# open-rally-computer.net
KiCad netlist of a schematic drawn in EasyEDA
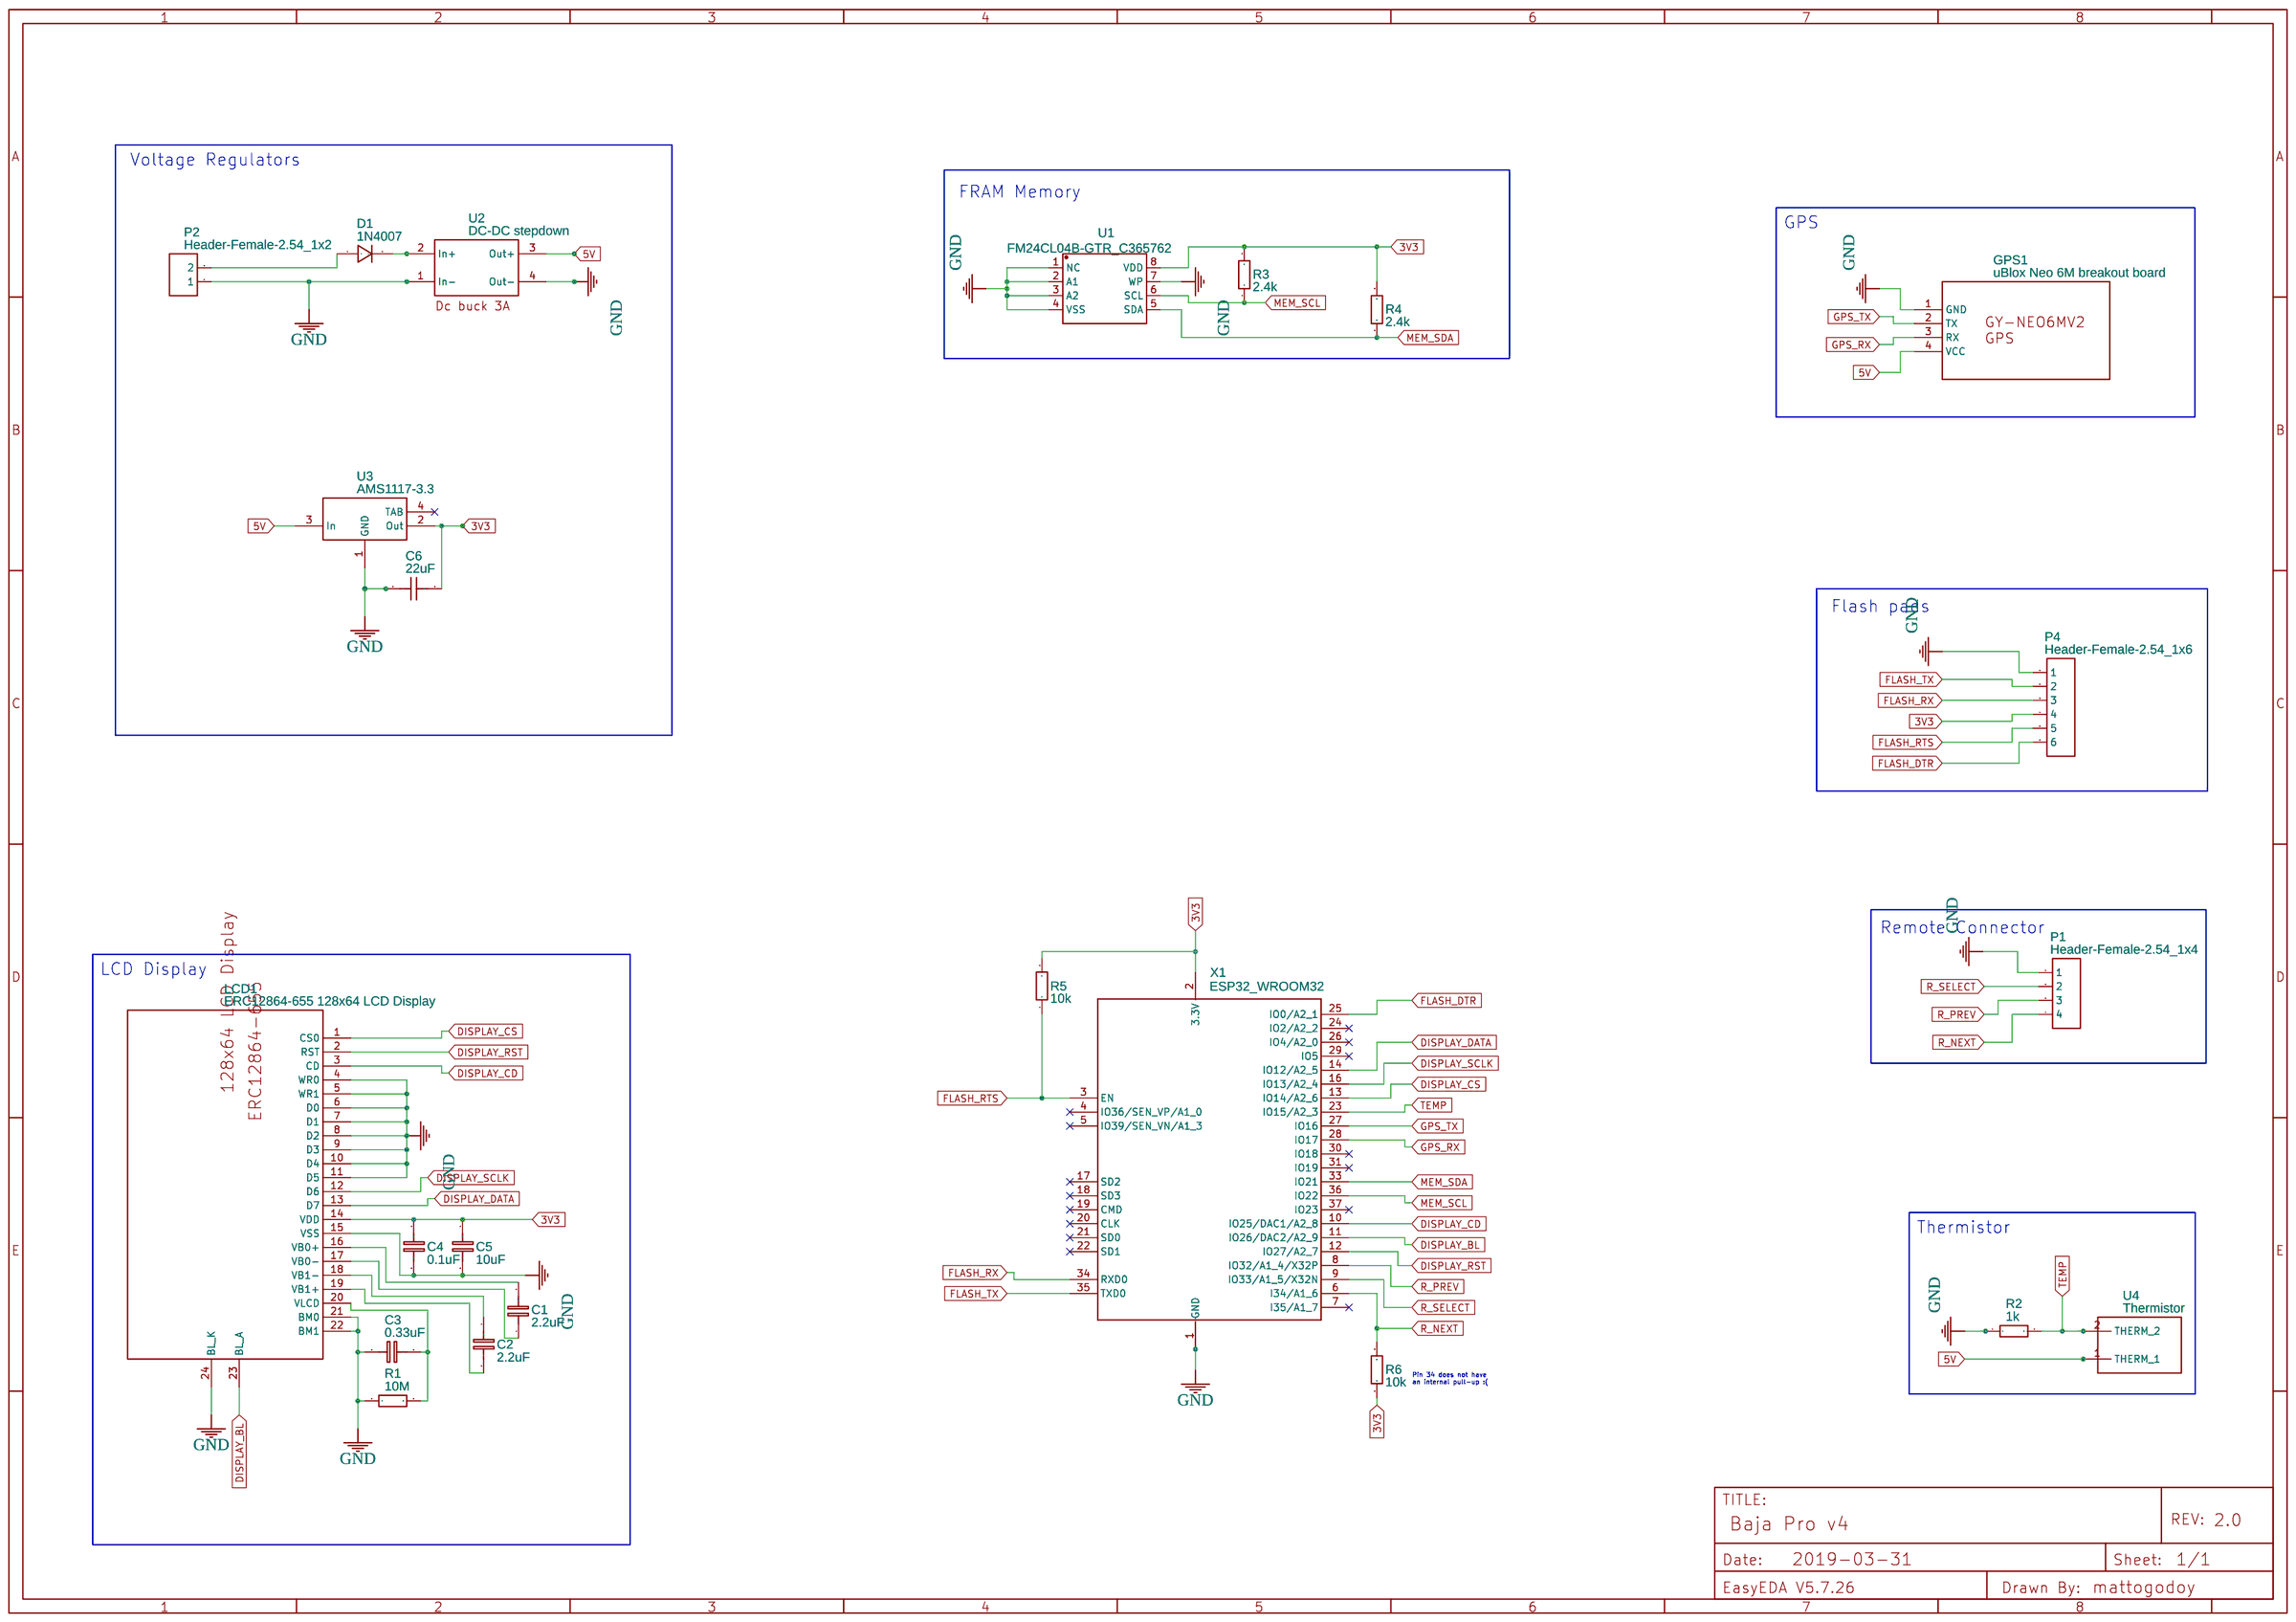
[diagram p0: schematic sheet]

(export (version "E")
  (design (tool "Eeschema 10.0.6"))
  (components
    (comp (ref "C1")
      (value "2.2uF")
      (fields (field (name "BOM_Manufacturer Part") "?"))
      (libsource (lib "") (part "Cap_1206_EU_1"))
    )
    (comp (ref "C2")
      (value "2.2uF")
      (fields (field (name "BOM_Manufacturer Part") "?"))
      (libsource (lib "") (part "Cap_1206_EU"))
    )
    (comp (ref "C3")
      (value "0.33uF")
      (fields (field (name "BOM_Manufacturer Part") "?"))
      (libsource (lib "") (part "Cap_1206_EU_2"))
    )
    (comp (ref "C4")
      (value "0.1uF")
      (fields (field (name "BOM_Manufacturer Part") "?"))
      (libsource (lib "") (part "Cap_1206_EU"))
    )
    (comp (ref "C5")
      (value "10uF")
      (fields (field (name "BOM_Manufacturer Part") "?"))
      (libsource (lib "") (part "Cap_1206_EU"))
    )
    (comp (ref "C6")
      (value "22uF")
      (fields
        (field (name "BOM_Manufacturer Part") "1206B226K160NT")
        (field (name "BOM_Supplier Part") "C31847")
      )
      (libsource (lib "") (part "1206B226K160NT"))
    )
    (comp (ref "D1")
      (value "1N4007")
      (fields (field (name "BOM_Supplier Part") "C181127"))
      (libsource (lib "") (part "Unknown_255_175"))
    )
    (comp (ref "GPS1")
      (value "uBlox Neo 6M breakout board")
      (fields (field (name "BOM_Manufacturer Part") "GY-NEO6MV2"))
      (libsource (lib "") (part "Unknown_1385_195"))
    )
    (comp (ref "LCD1")
      (value "ERC12864-655 128x64 LCD Display")
      (fields (field (name "BOM_Manufacturer Part") "ERC12864-655"))
      (libsource (lib "") (part "Unknown_155_837"))
    )
    (comp (ref "P1")
      (value "Header-Female-2.54_1x4")
      (fields (field (name "BOM_Supplier Part") "C124413"))
      (libsource (lib "") (part "Unknown_1469_705"))
    )
    (comp (ref "P2")
      (value "Header-Female-2.54_1x2")
      (fields
        (field (name "BOM_Manufacturer Part") "2.54-1*2PFemale")
        (field (name "BOM_Supplier Part") "C49661")
      )
      (libsource (lib "") (part "Unknown_130_190"))
    )
    (comp (ref "P4")
      (value "Header-Female-2.54_1x6")
      (fields
        (field (name "BOM_Manufacturer Part") "Female header 1*6p")
        (field (name "BOM_Supplier Part") "C40877")
      )
      (libsource (lib "") (part "Unknown_1465_500"))
    )
    (comp (ref "R1")
      (value "10M")
      (fields (field (name "BOM_Manufacturer Part") "?"))
      (libsource (lib "") (part "Res_1206(1/4W)_EU_1"))
    )
    (comp (ref "R2")
      (value "1k")
      (fields (field (name "BOM_Manufacturer Part") "?"))
      (libsource (lib "") (part "Res_1206(1/4W)_EU_3"))
    )
    (comp (ref "R3")
      (value "2.4k")
      (fields (field (name "BOM_Manufacturer Part") "?"))
      (libsource (lib "") (part "Res_1206(1/4W)_EU_2"))
    )
    (comp (ref "R4")
      (value "2.4k")
      (fields (field (name "BOM_Manufacturer Part") "?"))
      (libsource (lib "") (part "Res_1206(1/4W)_EU_2"))
    )
    (comp (ref "R5")
      (value "10k")
      (fields (field (name "BOM_Manufacturer Part") "?"))
      (libsource (lib "") (part "Res_1206(1/4W)_EU"))
    )
    (comp (ref "R6")
      (value "10k")
      (fields (field (name "BOM_Manufacturer Part") "?"))
      (libsource (lib "") (part "Res_1206(1/4W)_EU"))
    )
    (comp (ref "U1")
      (value "FM24CL04B-GTR_C365762")
      (fields
        (field (name "BOM_Manufacturer Part") "FM24CL04B-GTR")
        (field (name "BOM_Supplier Part") "C365762")
      )
      (libsource (lib "") (part "Unknown_785_200"))
    )
    (comp (ref "U2")
      (value "DC-DC stepdown")
      (fields (field (name "BOM_Manufacturer Part") "?"))
      (libsource (lib "") (part "Unknown_365_205"))
    )
    (comp (ref "U3")
      (value "AMS1117-3.3")
      (fields (field (name "BOM_Supplier Part") "C6186"))
      (libsource (lib "") (part "Unknown_255_375"))
    )
    (comp (ref "U4")
      (value "Thermistor")
      (fields (field (name "BOM_Manufacturer Part") "?"))
      (libsource (lib "") (part "Unknown_1506_957"))
    )
    (comp (ref "X1")
      (value "ESP32_WROOM32")
      (fields (field (name "BOM_Manufacturer Part") "?"))
      (libsource (lib "") (part "Unknown_850_940"))
    )
  )
  (nets
    (net (code "1") (name "3V3") (class "Default")
      (node (ref "C4") (pin "1") (pinfunction "1_1") (pintype "unspecified"))
      (node (ref "C5") (pin "1") (pinfunction "1_1") (pintype "unspecified"))
      (node (ref "C6") (pin "2") (pinfunction "2_2") (pintype "unspecified"))
      (node (ref "LCD1") (pin "14") (pinfunction "VDD_14") (pintype "unspecified"))
      (node (ref "P4") (pin "4") (pinfunction "4_4") (pintype "input"))
      (node (ref "R3") (pin "2") (pinfunction "2_2") (pintype "unspecified"))
      (node (ref "R4") (pin "2") (pinfunction "2_2") (pintype "unspecified"))
      (node (ref "R5") (pin "2") (pinfunction "2_2") (pintype "unspecified"))
      (node (ref "R6") (pin "1") (pinfunction "1_1") (pintype "unspecified"))
      (node (ref "U1") (pin "8") (pinfunction "VDD_8") (pintype "unspecified"))
      (node (ref "U3") (pin "2") (pinfunction "Out_2") (pintype "unspecified"))
      (node (ref "X1") (pin "2") (pinfunction "3.3V_2") (pintype "bidirectional"))
    )
    (net (code "2") (name "5V") (class "Default")
      (node (ref "GPS1") (pin "4") (pinfunction "VCC_4") (pintype "unspecified"))
      (node (ref "U2") (pin "3") (pinfunction "Out+_3") (pintype "unspecified"))
      (node (ref "U3") (pin "3") (pinfunction "In_3") (pintype "unspecified"))
      (node (ref "U4") (pin "1") (pinfunction "THERM_1_1") (pintype "unspecified"))
    )
    (net (code "3") (name "DISPLAY_BL") (class "Default")
      (node (ref "LCD1") (pin "23") (pinfunction "BL_A_23") (pintype "unspecified"))
      (node (ref "X1") (pin "11") (pinfunction "IO26/DAC2/A2_9_11") (pintype "bidirectional"))
    )
    (net (code "4") (name "DISPLAY_CD") (class "Default")
      (node (ref "LCD1") (pin "3") (pinfunction "CD_3") (pintype "unspecified"))
      (node (ref "X1") (pin "10") (pinfunction "IO25/DAC1/A2_8_10") (pintype "bidirectional"))
    )
    (net (code "5") (name "DISPLAY_CS") (class "Default")
      (node (ref "LCD1") (pin "1") (pinfunction "CS0_1") (pintype "unspecified"))
      (node (ref "X1") (pin "13") (pinfunction "IO14/A2_6_13") (pintype "bidirectional"))
    )
    (net (code "6") (name "DISPLAY_DATA") (class "Default")
      (node (ref "LCD1") (pin "13") (pinfunction "D7_13") (pintype "unspecified"))
      (node (ref "X1") (pin "14") (pinfunction "IO12/A2_5_14") (pintype "bidirectional"))
    )
    (net (code "7") (name "DISPLAY_RST") (class "Default")
      (node (ref "LCD1") (pin "2") (pinfunction "RST_2") (pintype "unspecified"))
      (node (ref "X1") (pin "12") (pinfunction "IO27/A2_7_12") (pintype "bidirectional"))
    )
    (net (code "8") (name "DISPLAY_SCLK") (class "Default")
      (node (ref "LCD1") (pin "12") (pinfunction "D6_12") (pintype "unspecified"))
      (node (ref "X1") (pin "16") (pinfunction "IO13/A2_4_16") (pintype "bidirectional"))
    )
    (net (code "9") (name "FLASH_DTR") (class "Default")
      (node (ref "P4") (pin "6") (pinfunction "6_6") (pintype "input"))
      (node (ref "X1") (pin "25") (pinfunction "IO0/A2_1_25") (pintype "bidirectional"))
    )
    (net (code "10") (name "FLASH_RTS") (class "Default")
      (node (ref "P4") (pin "5") (pinfunction "5_5") (pintype "input"))
      (node (ref "R5") (pin "1") (pinfunction "1_1") (pintype "unspecified"))
      (node (ref "X1") (pin "3") (pinfunction "EN_3") (pintype "bidirectional"))
    )
    (net (code "11") (name "FLASH_RX") (class "Default")
      (node (ref "P4") (pin "3") (pinfunction "3_3") (pintype "input"))
      (node (ref "X1") (pin "34") (pinfunction "RXD0_34") (pintype "bidirectional"))
    )
    (net (code "12") (name "FLASH_TX") (class "Default")
      (node (ref "P4") (pin "2") (pinfunction "2_2") (pintype "input"))
      (node (ref "X1") (pin "35") (pinfunction "TXD0_35") (pintype "bidirectional"))
    )
    (net (code "13") (name "GND") (class "Default")
      (node (ref "C3") (pin "1") (pinfunction "1_1") (pintype "unspecified"))
      (node (ref "C4") (pin "2") (pinfunction "2_2") (pintype "unspecified"))
      (node (ref "C5") (pin "2") (pinfunction "2_2") (pintype "unspecified"))
      (node (ref "C6") (pin "1") (pinfunction "1_1") (pintype "unspecified"))
      (node (ref "GPS1") (pin "1") (pinfunction "GND_1") (pintype "unspecified"))
      (node (ref "LCD1") (pin "10") (pinfunction "D4_10") (pintype "unspecified"))
      (node (ref "LCD1") (pin "11") (pinfunction "D5_11") (pintype "unspecified"))
      (node (ref "LCD1") (pin "15") (pinfunction "VSS_15") (pintype "unspecified"))
      (node (ref "LCD1") (pin "21") (pinfunction "BM0_21") (pintype "unspecified"))
      (node (ref "LCD1") (pin "22") (pinfunction "BM1_22") (pintype "unspecified"))
      (node (ref "LCD1") (pin "24") (pinfunction "BL_K_24") (pintype "unspecified"))
      (node (ref "LCD1") (pin "4") (pinfunction "WR0_4") (pintype "unspecified"))
      (node (ref "LCD1") (pin "5") (pinfunction "WR1_5") (pintype "unspecified"))
      (node (ref "LCD1") (pin "6") (pinfunction "D0_6") (pintype "unspecified"))
      (node (ref "LCD1") (pin "7") (pinfunction "D1_7") (pintype "unspecified"))
      (node (ref "LCD1") (pin "8") (pinfunction "D2_8") (pintype "unspecified"))
      (node (ref "LCD1") (pin "9") (pinfunction "D3_9") (pintype "unspecified"))
      (node (ref "P1") (pin "1") (pinfunction "1_1") (pintype "input"))
      (node (ref "P2") (pin "1") (pinfunction "1_1") (pintype "input"))
      (node (ref "P4") (pin "1") (pinfunction "1_1") (pintype "input"))
      (node (ref "R1") (pin "1") (pinfunction "1_1") (pintype "unspecified"))
      (node (ref "R2") (pin "1") (pinfunction "1_1") (pintype "unspecified"))
      (node (ref "U1") (pin "1") (pinfunction "NC_1") (pintype "unspecified"))
      (node (ref "U1") (pin "2") (pinfunction "A1_2") (pintype "unspecified"))
      (node (ref "U1") (pin "3") (pinfunction "A2_3") (pintype "unspecified"))
      (node (ref "U1") (pin "4") (pinfunction "VSS_4") (pintype "unspecified"))
      (node (ref "U1") (pin "7") (pinfunction "WP_7") (pintype "unspecified"))
      (node (ref "U2") (pin "1") (pinfunction "In-_1") (pintype "unspecified"))
      (node (ref "U2") (pin "4") (pinfunction "Out-_4") (pintype "unspecified"))
      (node (ref "U3") (pin "1") (pinfunction "GND_1") (pintype "unspecified"))
      (node (ref "X1") (pin "1") (pinfunction "GND_1") (pintype "bidirectional"))
      (node (ref "X1") (pin "15") (pinfunction "GND_15") (pintype "bidirectional"))
      (node (ref "X1") (pin "38") (pinfunction "GND_38") (pintype "bidirectional"))
      (node (ref "X1") (pin "P$1") (pinfunction "GND_P$1") (pintype "bidirectional"))
    )
    (net (code "14") (name "GPS_RX") (class "Default")
      (node (ref "GPS1") (pin "3") (pinfunction "RX_3") (pintype "unspecified"))
      (node (ref "X1") (pin "28") (pinfunction "IO17_28") (pintype "bidirectional"))
    )
    (net (code "15") (name "GPS_TX") (class "Default")
      (node (ref "GPS1") (pin "2") (pinfunction "TX_2") (pintype "unspecified"))
      (node (ref "X1") (pin "27") (pinfunction "IO16_27") (pintype "bidirectional"))
    )
    (net (code "16") (name "MEM_SCL") (class "Default")
      (node (ref "R3") (pin "1") (pinfunction "1_1") (pintype "unspecified"))
      (node (ref "U1") (pin "6") (pinfunction "SCL_6") (pintype "unspecified"))
      (node (ref "X1") (pin "36") (pinfunction "IO22_36") (pintype "bidirectional"))
    )
    (net (code "17") (name "MEM_SDA") (class "Default")
      (node (ref "R4") (pin "1") (pinfunction "1_1") (pintype "unspecified"))
      (node (ref "U1") (pin "5") (pinfunction "SDA_5") (pintype "unspecified"))
      (node (ref "X1") (pin "33") (pinfunction "IO21_33") (pintype "bidirectional"))
    )
    (net (code "18") (name "Net-(D1-+)") (class "Default")
      (node (ref "D1") (pin "1") (pinfunction "+_1") (pintype "unspecified"))
      (node (ref "P2") (pin "2") (pinfunction "2_2") (pintype "input"))
    )
    (net (code "19") (name "Net-(D1--)") (class "Default")
      (node (ref "D1") (pin "2") (pinfunction "-_2") (pintype "unspecified"))
      (node (ref "U2") (pin "2") (pinfunction "In+_2") (pintype "unspecified"))
    )
    (net (code "20") (name "Net-(LCD1-VB0+)") (class "Default")
      (node (ref "C1") (pin "2") (pinfunction "2_2") (pintype "unspecified"))
      (node (ref "LCD1") (pin "16") (pinfunction "VB0+_16") (pintype "unspecified"))
    )
    (net (code "21") (name "Net-(LCD1-VB0-)") (class "Default")
      (node (ref "C1") (pin "1") (pinfunction "1_1") (pintype "unspecified"))
      (node (ref "LCD1") (pin "17") (pinfunction "VB0-_17") (pintype "unspecified"))
    )
    (net (code "22") (name "Net-(LCD1-VB1+)") (class "Default")
      (node (ref "C2") (pin "2") (pinfunction "2_2") (pintype "unspecified"))
      (node (ref "LCD1") (pin "19") (pinfunction "VB1+_19") (pintype "unspecified"))
    )
    (net (code "23") (name "Net-(LCD1-VB1-)") (class "Default")
      (node (ref "C2") (pin "1") (pinfunction "1_1") (pintype "unspecified"))
      (node (ref "LCD1") (pin "18") (pinfunction "VB1-_18") (pintype "unspecified"))
    )
    (net (code "24") (name "Net-(LCD1-VLCD)") (class "Default")
      (node (ref "C3") (pin "2") (pinfunction "2_2") (pintype "unspecified"))
      (node (ref "LCD1") (pin "20") (pinfunction "VLCD_20") (pintype "unspecified"))
      (node (ref "R1") (pin "2") (pinfunction "2_2") (pintype "unspecified"))
    )
    (net (code "25") (name "R_NEXT") (class "Default")
      (node (ref "P1") (pin "4") (pinfunction "4_4") (pintype "input"))
      (node (ref "R6") (pin "2") (pinfunction "2_2") (pintype "unspecified"))
      (node (ref "X1") (pin "6") (pinfunction "I34/A1_6_6") (pintype "bidirectional"))
    )
    (net (code "26") (name "R_PREV") (class "Default")
      (node (ref "P1") (pin "3") (pinfunction "3_3") (pintype "input"))
      (node (ref "X1") (pin "8") (pinfunction "IO32/A1_4/X32P_8") (pintype "bidirectional"))
    )
    (net (code "27") (name "R_SELECT") (class "Default")
      (node (ref "P1") (pin "2") (pinfunction "2_2") (pintype "input"))
      (node (ref "X1") (pin "9") (pinfunction "IO33/A1_5/X32N_9") (pintype "bidirectional"))
    )
    (net (code "28") (name "TEMP") (class "Default")
      (node (ref "R2") (pin "2") (pinfunction "2_2") (pintype "unspecified"))
      (node (ref "U4") (pin "2") (pinfunction "THERM_2_2") (pintype "unspecified"))
      (node (ref "X1") (pin "23") (pinfunction "IO15/A2_3_23") (pintype "bidirectional"))
    )
    (net (code "29") (name "unconnected-(U3-TAB-Pad4)") (class "Default")
      (node (ref "U3") (pin "4") (pinfunction "TAB_4") (pintype "unspecified+no_connect"))
    )
    (net (code "30") (name "unconnected-(X1-CLK-Pad20)") (class "Default")
      (node (ref "X1") (pin "20") (pinfunction "CLK_20") (pintype "bidirectional+no_connect"))
    )
    (net (code "31") (name "unconnected-(X1-CMD-Pad19)") (class "Default")
      (node (ref "X1") (pin "19") (pinfunction "CMD_19") (pintype "bidirectional+no_connect"))
    )
    (net (code "32") (name "unconnected-(X1-I35{slash}A1_7-Pad7)") (class "Default")
      (node (ref "X1") (pin "7") (pinfunction "I35/A1_7_7") (pintype "bidirectional+no_connect"))
    )
    (net (code "33") (name "unconnected-(X1-IO2{slash}A2_2-Pad24)") (class "Default")
      (node (ref "X1") (pin "24") (pinfunction "IO2/A2_2_24") (pintype "bidirectional+no_connect"))
    )
    (net (code "34") (name "unconnected-(X1-IO4{slash}A2_0-Pad26)") (class "Default")
      (node (ref "X1") (pin "26") (pinfunction "IO4/A2_0_26") (pintype "bidirectional+no_connect"))
    )
    (net (code "35") (name "unconnected-(X1-IO5-Pad29)") (class "Default")
      (node (ref "X1") (pin "29") (pinfunction "IO5_29") (pintype "bidirectional+no_connect"))
    )
    (net (code "36") (name "unconnected-(X1-IO18-Pad30)") (class "Default")
      (node (ref "X1") (pin "30") (pinfunction "IO18_30") (pintype "bidirectional+no_connect"))
    )
    (net (code "37") (name "unconnected-(X1-IO19-Pad31)") (class "Default")
      (node (ref "X1") (pin "31") (pinfunction "IO19_31") (pintype "bidirectional+no_connect"))
    )
    (net (code "38") (name "unconnected-(X1-IO23-Pad37)") (class "Default")
      (node (ref "X1") (pin "37") (pinfunction "IO23_37") (pintype "bidirectional+no_connect"))
    )
    (net (code "39") (name "unconnected-(X1-IO36{slash}SEN_VP{slash}A1_0-Pad4)") (class "Default")
      (node (ref "X1") (pin "4") (pinfunction "IO36/SEN_VP/A1_0_4") (pintype "bidirectional+no_connect"))
    )
    (net (code "40") (name "unconnected-(X1-IO39{slash}SEN_VN{slash}A1_3-Pad5)") (class "Default")
      (node (ref "X1") (pin "5") (pinfunction "IO39/SEN_VN/A1_3_5") (pintype "bidirectional+no_connect"))
    )
    (net (code "41") (name "unconnected-(X1-SD0-Pad21)") (class "Default")
      (node (ref "X1") (pin "21") (pinfunction "SD0_21") (pintype "bidirectional+no_connect"))
    )
    (net (code "42") (name "unconnected-(X1-SD1-Pad22)") (class "Default")
      (node (ref "X1") (pin "22") (pinfunction "SD1_22") (pintype "bidirectional+no_connect"))
    )
    (net (code "43") (name "unconnected-(X1-SD2-Pad17)") (class "Default")
      (node (ref "X1") (pin "17") (pinfunction "SD2_17") (pintype "bidirectional+no_connect"))
    )
    (net (code "44") (name "unconnected-(X1-SD3-Pad18)") (class "Default")
      (node (ref "X1") (pin "18") (pinfunction "SD3_18") (pintype "bidirectional+no_connect"))
    )
  )
)
